# USB_HUB1_UP_PORT0.net
KiCad netlist of a schematic drawn in Altium Designer
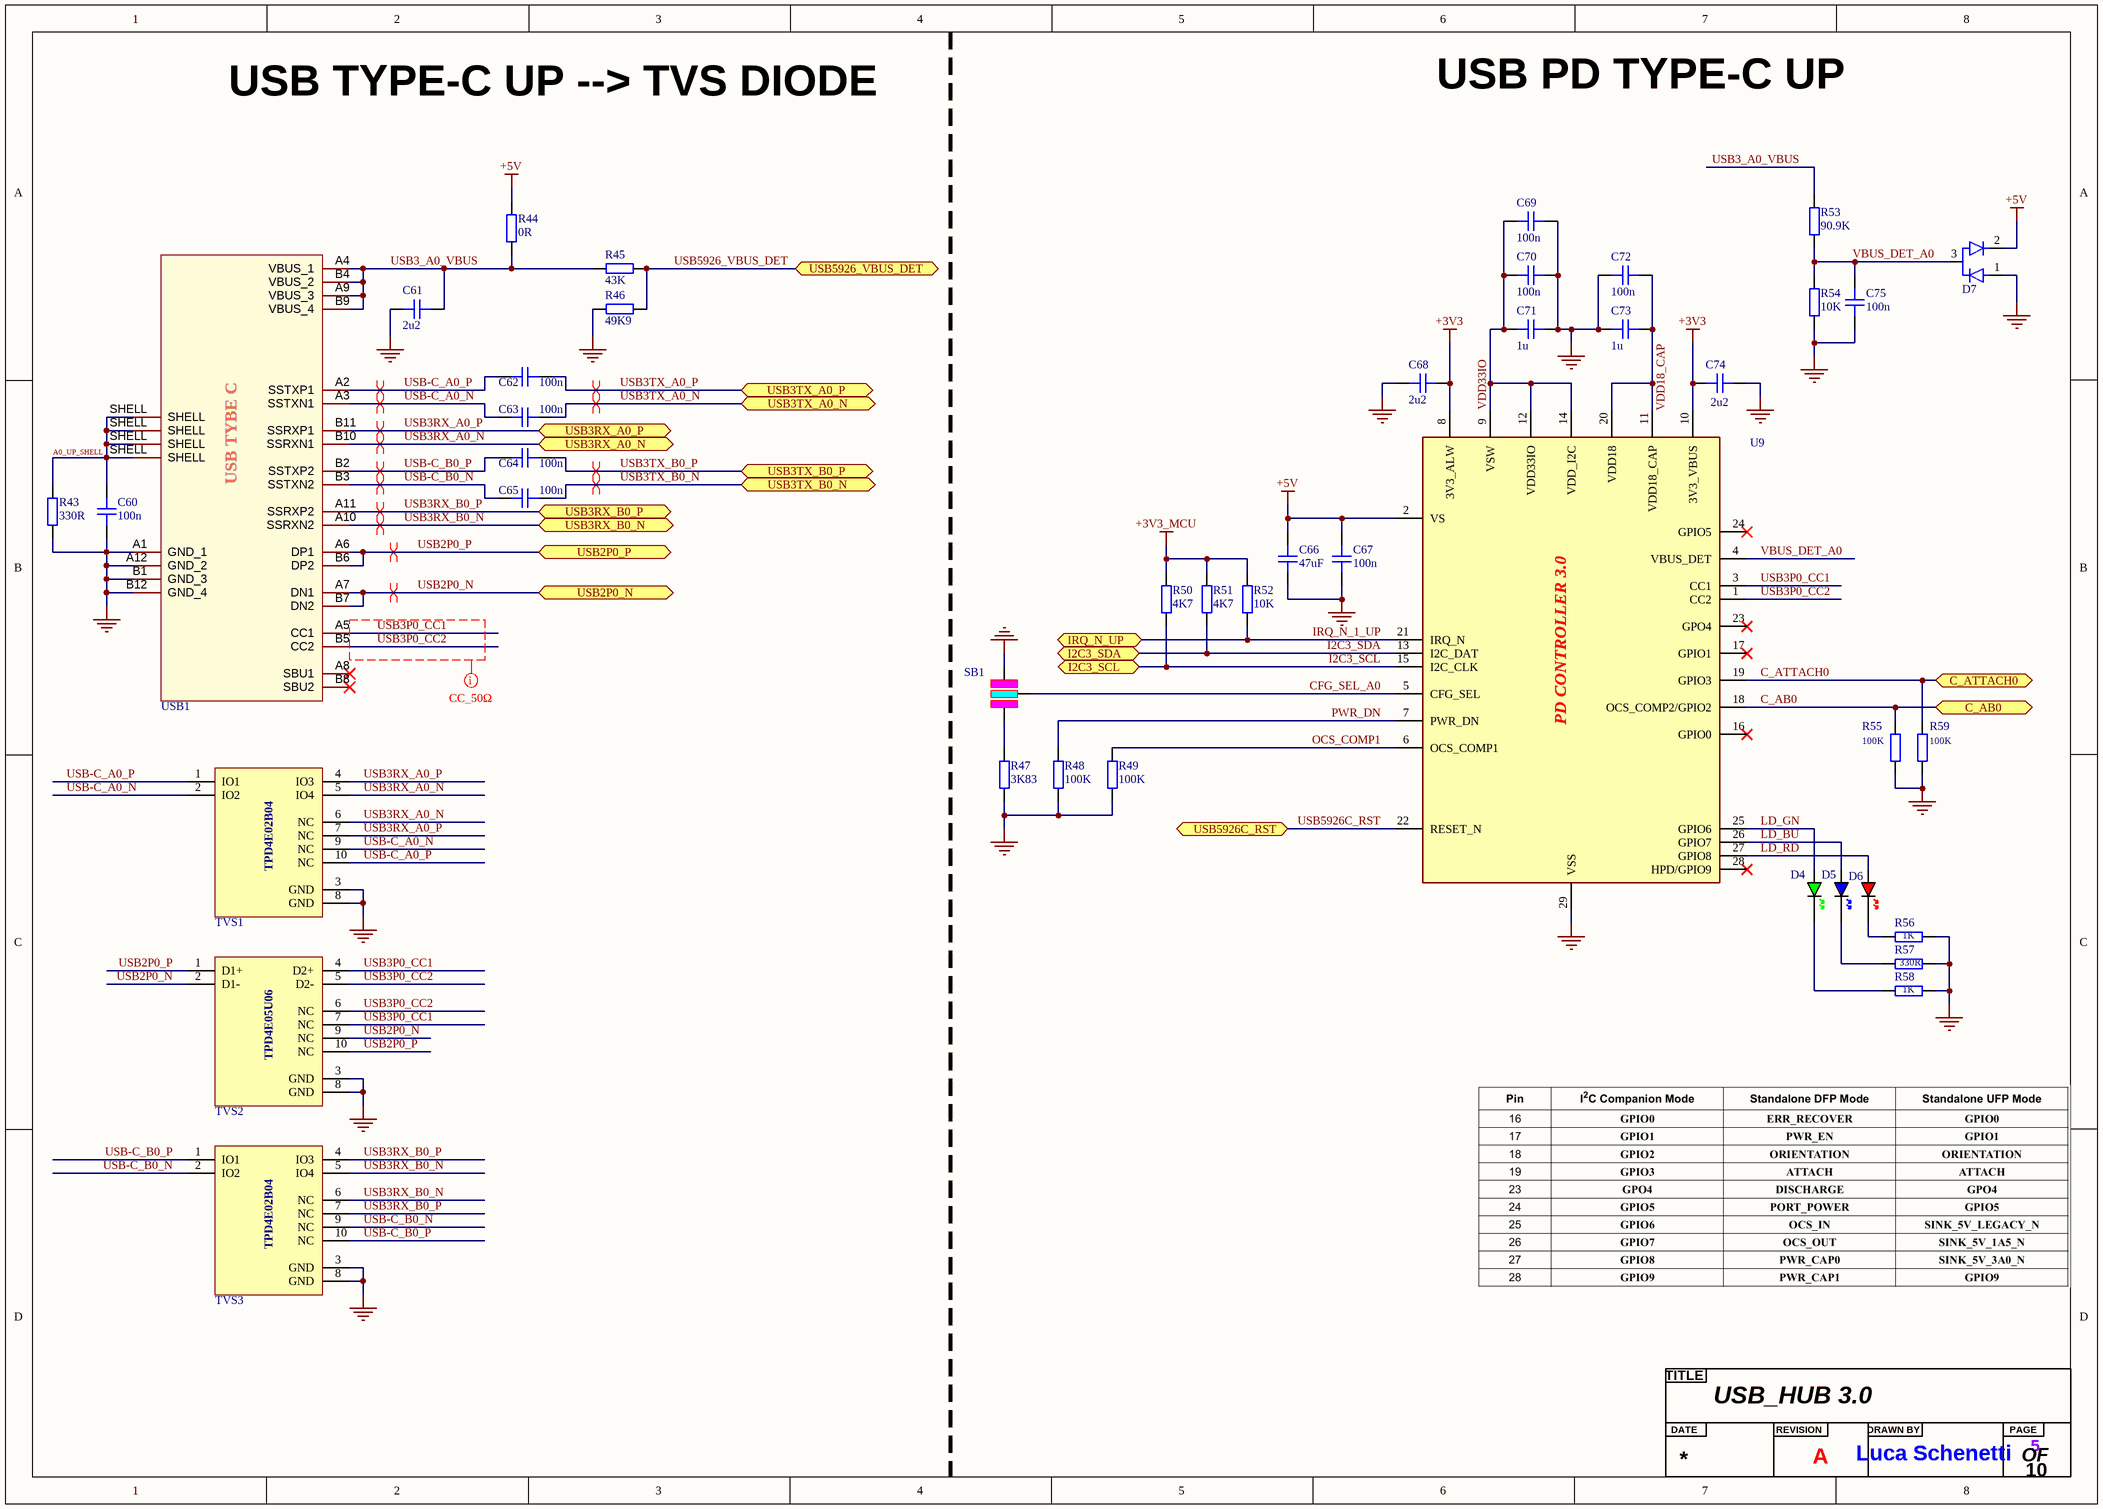
[diagram p0: USB_HUB1 UP PORT0.SchDoc]

(export (version "E")
  (design (tool "Eeschema 10.0.6"))
  (components
    (comp (ref "C60")
      (value "100n")
      (footprint "CAP_0603")
      (description "Capacitor SMD 0603 [C14663]")
      (libsource (lib "Schematic-Lib-PhilsLab") (part "CAP_0603"))
    )
    (comp (ref "C61")
      (value "2u2")
      (footprint "CAP_0603")
      (description "Capacitor SMD 0603 [C23630]")
      (libsource (lib "Schematic-Lib-PhilsLab") (part "CAP_0603"))
    )
    (comp (ref "C62")
      (value "100n")
      (footprint "CAP_0402")
      (description "Capacitor SMD 0402[C1525]")
      (libsource (lib "Schematic-Lib-PhilsLab") (part "CAP_0402"))
    )
    (comp (ref "C63")
      (value "100n")
      (footprint "CAP_0402")
      (description "Capacitor SMD 0402[C1525]")
      (libsource (lib "Schematic-Lib-PhilsLab") (part "CAP_0402"))
    )
    (comp (ref "C64")
      (value "100n")
      (footprint "CAP_0402")
      (description "Capacitor SMD 0402[C1525]")
      (libsource (lib "Schematic-Lib-PhilsLab") (part "CAP_0402"))
    )
    (comp (ref "C65")
      (value "100n")
      (footprint "CAP_0402")
      (description "Capacitor SMD 0402[C1525]")
      (libsource (lib "Schematic-Lib-PhilsLab") (part "CAP_0402"))
    )
    (comp (ref "C66")
      (value "47uF")
      (footprint "CAP_0603")
      (description "Capacitor SMD 0603 [C730416]")
      (libsource (lib "Schematic-Lib-PhilsLab") (part "CAP_0603"))
    )
    (comp (ref "C67")
      (value "100n")
      (footprint "CAP_0603")
      (description "Capacitor SMD 0603 [C14663]")
      (libsource (lib "Schematic-Lib-PhilsLab") (part "CAP_0603"))
    )
    (comp (ref "C68")
      (value "2u2")
      (footprint "CAP_0603")
      (description "Capacitor SMD 0603 [C23630]")
      (libsource (lib "Schematic-Lib-PhilsLab") (part "CAP_0603"))
    )
    (comp (ref "C69")
      (value "100n")
      (footprint "CAP_0603")
      (description "Capacitor SMD 0603 [C14663]")
      (libsource (lib "Schematic-Lib-PhilsLab") (part "CAP_0603"))
    )
    (comp (ref "C70")
      (value "100n")
      (footprint "CAP_0603")
      (description "Capacitor SMD 0603 [C14663]")
      (libsource (lib "Schematic-Lib-PhilsLab") (part "CAP_0603"))
    )
    (comp (ref "C71")
      (value "1u")
      (footprint "CAP_0603")
      (description "Capacitor SMD 0603 [C15849]")
      (libsource (lib "Schematic-Lib-PhilsLab") (part "CAP_0603"))
    )
    (comp (ref "C72")
      (value "100n")
      (footprint "CAP_0603")
      (description "Capacitor SMD 0603 [C14663]")
      (libsource (lib "Schematic-Lib-PhilsLab") (part "CAP_0603"))
    )
    (comp (ref "C73")
      (value "1u")
      (footprint "CAP_0603")
      (description "Capacitor SMD 0603 [C15849]")
      (libsource (lib "Schematic-Lib-PhilsLab") (part "CAP_0603"))
    )
    (comp (ref "C74")
      (value "2u2")
      (footprint "CAP_0603")
      (description "Capacitor SMD 0603 [C23630]")
      (libsource (lib "Schematic-Lib-PhilsLab") (part "CAP_0603"))
    )
    (comp (ref "C75")
      (value "100n")
      (footprint "CAP_0603")
      (description "Capacitor SMD 0603 [C14663]")
      (libsource (lib "Schematic-Lib-PhilsLab") (part "CAP_0603"))
    )
    (comp (ref "D4")
      (value "GREEN")
      (footprint "LED_0603_GREEN")
      (description "[C2986059]")
      (libsource (lib "Schematic-Lib-PhilsLab") (part "LED_0603_GREEN"))
    )
    (comp (ref "D5")
      (value "BLUE")
      (footprint "LED_0603_BLUE")
      (description "[C84266]")
      (libsource (lib "Schematic-Lib-PhilsLab") (part "LED_0603_BLUE"))
    )
    (comp (ref "D6")
      (value "RED")
      (footprint "LED_0603_RED")
      (description "[C2286]")
      (libsource (lib "Schematic-Lib-PhilsLab") (part "LED_0603_RED"))
    )
    (comp (ref "D7")
      (value "High-Speed Switching Diode")
      (footprint "BAV99,215")
      (description "[C2500]")
      (libsource (lib "My_Library") (part "BAV99,215"))
    )
    (comp (ref "R43")
      (value "330R")
      (footprint "RES_0603")
      (description "[C23138]")
      (libsource (lib "Schematic-Lib-PhilsLab") (part "RES_0603"))
    )
    (comp (ref "R44")
      (value "0R")
      (footprint "RES_0603")
      (description "[C21189]")
      (libsource (lib "Schematic-Lib-PhilsLab") (part "RES_0603"))
    )
    (comp (ref "R45")
      (value "43K")
      (footprint "RES_0603")
      (description "[C23172]")
      (libsource (lib "Schematic-Lib-PhilsLab") (part "RES_0603"))
    )
    (comp (ref "R46")
      (value "49K9")
      (footprint "RES_0603")
      (description "[C23184]")
      (libsource (lib "Schematic-Lib-PhilsLab") (part "RES_0603"))
    )
    (comp (ref "R47")
      (value "3K83")
      (footprint "RES_0603")
      (description "[C22982]")
      (libsource (lib "Schematic-Lib-PhilsLab") (part "RES_0603"))
    )
    (comp (ref "R48")
      (value "100K")
      (footprint "RES_0603")
      (description "[C25803]")
      (libsource (lib "Schematic-Lib-PhilsLab") (part "RES_0603"))
    )
    (comp (ref "R49")
      (value "100K")
      (footprint "RES_0603")
      (description "[C25803]")
      (libsource (lib "Schematic-Lib-PhilsLab") (part "RES_0603"))
    )
    (comp (ref "R50")
      (value "4K7")
      (footprint "RES_0603")
      (description "Resistor SMD 0603[C23162]")
      (libsource (lib "Schematic-Lib-PhilsLab") (part "RES_0603"))
    )
    (comp (ref "R51")
      (value "4K7")
      (footprint "RES_0603")
      (description "Resistor SMD 0603[C23162]")
      (libsource (lib "Schematic-Lib-PhilsLab") (part "RES_0603"))
    )
    (comp (ref "R52")
      (value "10K")
      (footprint "RES_0603")
      (description "Resistor SMD 0603[C25804]")
      (libsource (lib "Schematic-Lib-PhilsLab") (part "RES_0603"))
    )
    (comp (ref "R53")
      (value "90.9K")
      (footprint "RES_0603")
      (description "[C23129]")
      (libsource (lib "Schematic-Lib-PhilsLab") (part "RES_0603"))
    )
    (comp (ref "R54")
      (value "10K")
      (footprint "RES_0603")
      (description "[C25804]")
      (libsource (lib "Schematic-Lib-PhilsLab") (part "RES_0603"))
    )
    (comp (ref "R55")
      (value "100K")
      (footprint "RES_0603")
      (description "[C25803]")
      (libsource (lib "Schematic-Lib-PhilsLab") (part "RES_0603"))
    )
    (comp (ref "R56")
      (value "1K")
      (footprint "RES_0603")
      (description "[C21190]")
      (libsource (lib "Schematic-Lib-PhilsLab") (part "RES_0603"))
    )
    (comp (ref "R57")
      (value "330R")
      (footprint "RES_0603")
      (description "[C23138]")
      (libsource (lib "Schematic-Lib-PhilsLab") (part "RES_0603"))
    )
    (comp (ref "R58")
      (value "1K")
      (footprint "RES_0603")
      (description "[C21190]")
      (libsource (lib "Schematic-Lib-PhilsLab") (part "RES_0603"))
    )
    (comp (ref "R59")
      (value "100K")
      (footprint "RES_0603")
      (description "[C25803]")
      (libsource (lib "Schematic-Lib-PhilsLab") (part "RES_0603"))
    )
    (comp (ref "SB1")
      (value "SOLDER BBRIDGE 3W")
      (footprint "SOLDER BRIDBE 3W")
      (libsource (lib "My_Library") (part "SOLDER BBRIDGE 3W"))
    )
    (comp (ref "TVS1")
      (value "TVS DIODE USB 3")
      (footprint "TPD4E02B04DQAR")
      (description "[C106794]")
      (libsource (lib "My_Library") (part "TPD4E02B04DQAR"))
    )
    (comp (ref "TVS2")
      (value "ESD and Surge Protection USB, HDMI & High Speed")
      (footprint "TPD4E05U06DQAR")
      (description "[C138714]")
      (libsource (lib "My_Library") (part "TPD4E05U06DQAR"))
    )
    (comp (ref "TVS3")
      (value "TVS DIODE USB 3")
      (footprint "TPD4E02B04DQAR")
      (description "[C106794]")
      (libsource (lib "My_Library") (part "TPD4E02B04DQAR"))
    )
    (comp (ref "U9")
      (value "USB Type-C® PD 3.0 Port Controller")
      (footprint "UPD350AT/Q8X")
      (description "[C622602]")
      (libsource (lib "My_Library") (part "UPD350AT/Q8X"))
    )
    (comp (ref "USB1")
      (value "TYPE-C 24P QCHT")
      (footprint "TYPE-C 24P QCHT")
      (description "[C456013]")
      (libsource (lib "My_Library") (part "TYPE-C 24P QCHT"))
    )
  )
  (nets
    (net (code "1") (name "+3V3") (class "Default")
      (node (ref "C68") (pin "2") (pinfunction "2_2") (pintype "passive"))
      (node (ref "C74") (pin "2") (pinfunction "2_2") (pintype "passive"))
      (node (ref "U9") (pin "10") (pinfunction "3V3_VBUS_10") (pintype "passive"))
      (node (ref "U9") (pin "8") (pinfunction "3V3_ALW_8") (pintype "passive"))
    )
    (net (code "2") (name "+3V3_MCU") (class "Default")
      (node (ref "R50") (pin "2") (pinfunction "2_2") (pintype "passive"))
      (node (ref "R51") (pin "2") (pinfunction "2_2") (pintype "passive"))
      (node (ref "R52") (pin "2") (pinfunction "2_2") (pintype "passive"))
    )
    (net (code "3") (name "+5V") (class "Default")
      (node (ref "C66") (pin "2") (pinfunction "2_2") (pintype "passive"))
      (node (ref "C67") (pin "2") (pinfunction "2_2") (pintype "passive"))
      (node (ref "D7") (pin "2") (pinfunction "2_2") (pintype "passive"))
      (node (ref "R44") (pin "2") (pinfunction "2_2") (pintype "passive"))
      (node (ref "U9") (pin "2") (pinfunction "VS_2") (pintype "passive"))
    )
    (net (code "4") (name "/A0_UP_SHELL") (class "Default")
      (node (ref "C60") (pin "2") (pinfunction "2_2") (pintype "passive"))
      (node (ref "R43") (pin "2") (pinfunction "2_2") (pintype "passive"))
      (node (ref "USB1") (pin "SHELL") (pinfunction "SHELL_SHELL") (pintype "passive"))
    )
    (net (code "5") (name "/CFG_SEL_A0") (class "Default")
      (node (ref "SB1") (pin "1") (pinfunction "1_1") (pintype "passive"))
      (node (ref "U9") (pin "5") (pinfunction "CFG_SEL_5") (pintype "passive"))
    )
    (net (code "6") (name "/C_AB0") (class "Default")
      (node (ref "R55") (pin "2") (pinfunction "2_2") (pintype "passive"))
      (node (ref "U9") (pin "18") (pinfunction "OCS_COMP2/GPIO2_18") (pintype "passive"))
    )
    (net (code "7") (name "/C_ATTACH0") (class "Default")
      (node (ref "R59") (pin "2") (pinfunction "2_2") (pintype "passive"))
      (node (ref "U9") (pin "19") (pinfunction "GPIO3_19") (pintype "passive"))
    )
    (net (code "8") (name "/I2C3_SCL") (class "Default")
      (node (ref "R50") (pin "1") (pinfunction "1_1") (pintype "passive"))
      (node (ref "U9") (pin "15") (pinfunction "I2C_CLK_15") (pintype "passive"))
    )
    (net (code "9") (name "/I2C3_SDA") (class "Default")
      (node (ref "R51") (pin "1") (pinfunction "1_1") (pintype "passive"))
      (node (ref "U9") (pin "13") (pinfunction "I2C_DAT_13") (pintype "passive"))
    )
    (net (code "10") (name "/IRQ_N_1_UP") (class "Default")
      (node (ref "R52") (pin "1") (pinfunction "1_1") (pintype "passive"))
      (node (ref "U9") (pin "21") (pinfunction "IRQ_N_21") (pintype "passive"))
    )
    (net (code "12") (name "/LD_BU") (class "Default")
      (node (ref "D5") (pin "A") (pinfunction "A_A") (pintype "passive"))
      (node (ref "U9") (pin "26") (pinfunction "GPIO7_26") (pintype "passive"))
    )
    (net (code "13") (name "/LD_GN") (class "Default")
      (node (ref "D4") (pin "A") (pinfunction "A_A") (pintype "passive"))
      (node (ref "U9") (pin "25") (pinfunction "GPIO6_25") (pintype "passive"))
    )
    (net (code "14") (name "/LD_RD") (class "Default")
      (node (ref "D6") (pin "A") (pinfunction "A_A") (pintype "passive"))
      (node (ref "U9") (pin "27") (pinfunction "GPIO8_27") (pintype "passive"))
    )
    (net (code "15") (name "/OCS_COMP1") (class "Default")
      (node (ref "R49") (pin "2") (pinfunction "2_2") (pintype "passive"))
      (node (ref "U9") (pin "6") (pinfunction "OCS_COMP1_6") (pintype "passive"))
    )
    (net (code "16") (name "/PWR_DN") (class "Default")
      (node (ref "R48") (pin "2") (pinfunction "2_2") (pintype "passive"))
      (node (ref "U9") (pin "7") (pinfunction "PWR_DN_7") (pintype "passive"))
    )
    (net (code "17") (name "/USB-C_A0_N") (class "Default")
      (node (ref "C63") (pin "1") (pinfunction "1_1") (pintype "passive"))
      (node (ref "TVS1") (pin "2") (pinfunction "IO2_2") (pintype "passive"))
      (node (ref "TVS1") (pin "9") (pinfunction "NC_9") (pintype "passive"))
      (node (ref "USB1") (pin "A3") (pinfunction "SSTXN1_A3") (pintype "passive"))
    )
    (net (code "18") (name "/USB-C_A0_P") (class "Default")
      (node (ref "C62") (pin "1") (pinfunction "1_1") (pintype "passive"))
      (node (ref "TVS1") (pin "1") (pinfunction "IO1_1") (pintype "passive"))
      (node (ref "TVS1") (pin "10") (pinfunction "NC_10") (pintype "passive"))
      (node (ref "USB1") (pin "A2") (pinfunction "SSTXP1_A2") (pintype "passive"))
    )
    (net (code "19") (name "/USB-C_B0_N") (class "Default")
      (node (ref "C65") (pin "1") (pinfunction "1_1") (pintype "passive"))
      (node (ref "TVS3") (pin "2") (pinfunction "IO2_2") (pintype "passive"))
      (node (ref "TVS3") (pin "9") (pinfunction "NC_9") (pintype "passive"))
      (node (ref "USB1") (pin "B3") (pinfunction "SSTXN2_B3") (pintype "passive"))
    )
    (net (code "20") (name "/USB-C_B0_P") (class "Default")
      (node (ref "C64") (pin "1") (pinfunction "1_1") (pintype "passive"))
      (node (ref "TVS3") (pin "1") (pinfunction "IO1_1") (pintype "passive"))
      (node (ref "TVS3") (pin "10") (pinfunction "NC_10") (pintype "passive"))
      (node (ref "USB1") (pin "B2") (pinfunction "SSTXP2_B2") (pintype "passive"))
    )
    (net (code "21") (name "/USB2P0_N") (class "Default")
      (node (ref "TVS2") (pin "2") (pinfunction "D1-_2") (pintype "passive"))
      (node (ref "TVS2") (pin "9") (pinfunction "NC_9") (pintype "passive"))
      (node (ref "USB1") (pin "A7") (pinfunction "DN1_A7") (pintype "passive"))
      (node (ref "USB1") (pin "B7") (pinfunction "DN2_B7") (pintype "passive"))
    )
    (net (code "22") (name "/USB2P0_P") (class "Default")
      (node (ref "TVS2") (pin "1") (pinfunction "D1+_1") (pintype "passive"))
      (node (ref "TVS2") (pin "10") (pinfunction "NC_10") (pintype "passive"))
      (node (ref "USB1") (pin "A6") (pinfunction "DP1_A6") (pintype "passive"))
      (node (ref "USB1") (pin "B6") (pinfunction "DP2_B6") (pintype "passive"))
    )
    (net (code "23") (name "/USB3P0_CC1") (class "Default")
      (node (ref "TVS2") (pin "4") (pinfunction "D2+_4") (pintype "passive"))
      (node (ref "TVS2") (pin "7") (pinfunction "NC_7") (pintype "passive"))
      (node (ref "U9") (pin "3") (pinfunction "CC1_3") (pintype "passive"))
      (node (ref "USB1") (pin "A5") (pinfunction "CC1_A5") (pintype "passive"))
    )
    (net (code "24") (name "/USB3P0_CC2") (class "Default")
      (node (ref "TVS2") (pin "5") (pinfunction "D2-_5") (pintype "passive"))
      (node (ref "TVS2") (pin "6") (pinfunction "NC_6") (pintype "passive"))
      (node (ref "U9") (pin "1") (pinfunction "CC2_1") (pintype "passive"))
      (node (ref "USB1") (pin "B5") (pinfunction "CC2_B5") (pintype "passive"))
    )
    (net (code "25") (name "/USB3RX_A0_N") (class "Default")
      (node (ref "TVS1") (pin "5") (pinfunction "IO4_5") (pintype "passive"))
      (node (ref "TVS1") (pin "6") (pinfunction "NC_6") (pintype "passive"))
      (node (ref "USB1") (pin "B10") (pinfunction "SSRXN1_B10") (pintype "passive"))
    )
    (net (code "26") (name "/USB3RX_A0_P") (class "Default")
      (node (ref "TVS1") (pin "4") (pinfunction "IO3_4") (pintype "passive"))
      (node (ref "TVS1") (pin "7") (pinfunction "NC_7") (pintype "passive"))
      (node (ref "USB1") (pin "B11") (pinfunction "SSRXP1_B11") (pintype "passive"))
    )
    (net (code "27") (name "/USB3RX_B0_N") (class "Default")
      (node (ref "TVS3") (pin "5") (pinfunction "IO4_5") (pintype "passive"))
      (node (ref "TVS3") (pin "6") (pinfunction "NC_6") (pintype "passive"))
      (node (ref "USB1") (pin "A10") (pinfunction "SSRXN2_A10") (pintype "passive"))
    )
    (net (code "28") (name "/USB3RX_B0_P") (class "Default")
      (node (ref "TVS3") (pin "4") (pinfunction "IO3_4") (pintype "passive"))
      (node (ref "TVS3") (pin "7") (pinfunction "NC_7") (pintype "passive"))
      (node (ref "USB1") (pin "A11") (pinfunction "SSRXP2_A11") (pintype "passive"))
    )
    (net (code "29") (name "/USB3TX_A0_N") (class "Default")
      (node (ref "C63") (pin "2") (pinfunction "2_2") (pintype "passive"))
    )
    (net (code "30") (name "/USB3TX_A0_P") (class "Default")
      (node (ref "C62") (pin "2") (pinfunction "2_2") (pintype "passive"))
    )
    (net (code "31") (name "/USB3TX_B0_N") (class "Default")
      (node (ref "C65") (pin "2") (pinfunction "2_2") (pintype "passive"))
    )
    (net (code "32") (name "/USB3TX_B0_P") (class "Default")
      (node (ref "C64") (pin "2") (pinfunction "2_2") (pintype "passive"))
    )
    (net (code "33") (name "/USB3_A0_VBUS") (class "Default")
      (node (ref "C61") (pin "2") (pinfunction "2_2") (pintype "passive"))
      (node (ref "R44") (pin "1") (pinfunction "1_1") (pintype "passive"))
      (node (ref "R45") (pin "1") (pinfunction "1_1") (pintype "passive"))
      (node (ref "R53") (pin "2") (pinfunction "2_2") (pintype "passive"))
      (node (ref "USB1") (pin "A4") (pinfunction "VBUS_1_A4") (pintype "passive"))
      (node (ref "USB1") (pin "A9") (pinfunction "VBUS_3_A9") (pintype "passive"))
      (node (ref "USB1") (pin "B4") (pinfunction "VBUS_2_B4") (pintype "passive"))
      (node (ref "USB1") (pin "B9") (pinfunction "VBUS_4_B9") (pintype "passive"))
    )
    (net (code "34") (name "/USB5926C_RST") (class "Default")
      (node (ref "U9") (pin "22") (pinfunction "RESET_N_22") (pintype "passive"))
    )
    (net (code "35") (name "/USB5926_VBUS_DET") (class "Default")
      (node (ref "R45") (pin "2") (pinfunction "2_2") (pintype "passive"))
      (node (ref "R46") (pin "2") (pinfunction "2_2") (pintype "passive"))
    )
    (net (code "36") (name "/VBUS_DET_A0") (class "Default")
      (node (ref "C75") (pin "2") (pinfunction "2_2") (pintype "passive"))
      (node (ref "D7") (pin "3") (pinfunction "3_3") (pintype "passive"))
      (node (ref "R53") (pin "1") (pinfunction "1_1") (pintype "passive"))
      (node (ref "R54") (pin "2") (pinfunction "2_2") (pintype "passive"))
      (node (ref "U9") (pin "4") (pinfunction "VBUS_DET_4") (pintype "passive"))
    )
    (net (code "37") (name "/VDD18_CAP") (class "Default")
      (node (ref "C72") (pin "1") (pinfunction "1_1") (pintype "passive"))
      (node (ref "C73") (pin "2") (pinfunction "2_2") (pintype "passive"))
      (node (ref "U9") (pin "11") (pinfunction "VDD18_CAP_11") (pintype "passive"))
      (node (ref "U9") (pin "20") (pinfunction "VDD18_20") (pintype "passive"))
    )
    (net (code "38") (name "/VDD33IO") (class "Default")
      (node (ref "C69") (pin "2") (pinfunction "2_2") (pintype "passive"))
      (node (ref "C70") (pin "2") (pinfunction "2_2") (pintype "passive"))
      (node (ref "C71") (pin "2") (pinfunction "2_2") (pintype "passive"))
      (node (ref "U9") (pin "12") (pinfunction "VDD33IO_12") (pintype "passive"))
      (node (ref "U9") (pin "14") (pinfunction "VDD_I2C_14") (pintype "passive"))
      (node (ref "U9") (pin "9") (pinfunction "VSW_9") (pintype "passive"))
    )
    (net (code "39") (name "GND") (class "Default")
      (node (ref "C60") (pin "1") (pinfunction "1_1") (pintype "passive"))
      (node (ref "C61") (pin "1") (pinfunction "1_1") (pintype "passive"))
      (node (ref "C66") (pin "1") (pinfunction "1_1") (pintype "passive"))
      (node (ref "C67") (pin "1") (pinfunction "1_1") (pintype "passive"))
      (node (ref "C68") (pin "1") (pinfunction "1_1") (pintype "passive"))
      (node (ref "C69") (pin "1") (pinfunction "1_1") (pintype "passive"))
      (node (ref "C70") (pin "1") (pinfunction "1_1") (pintype "passive"))
      (node (ref "C71") (pin "1") (pinfunction "1_1") (pintype "passive"))
      (node (ref "C72") (pin "2") (pinfunction "2_2") (pintype "passive"))
      (node (ref "C73") (pin "1") (pinfunction "1_1") (pintype "passive"))
      (node (ref "C74") (pin "1") (pinfunction "1_1") (pintype "passive"))
      (node (ref "C75") (pin "1") (pinfunction "1_1") (pintype "passive"))
      (node (ref "D7") (pin "1") (pinfunction "1_1") (pintype "passive"))
      (node (ref "R43") (pin "1") (pinfunction "1_1") (pintype "passive"))
      (node (ref "R46") (pin "1") (pinfunction "1_1") (pintype "passive"))
      (node (ref "R47") (pin "1") (pinfunction "1_1") (pintype "passive"))
      (node (ref "R48") (pin "1") (pinfunction "1_1") (pintype "passive"))
      (node (ref "R49") (pin "1") (pinfunction "1_1") (pintype "passive"))
      (node (ref "R54") (pin "1") (pinfunction "1_1") (pintype "passive"))
      (node (ref "R55") (pin "1") (pinfunction "1_1") (pintype "passive"))
      (node (ref "R56") (pin "2") (pinfunction "2_2") (pintype "passive"))
      (node (ref "R57") (pin "2") (pinfunction "2_2") (pintype "passive"))
      (node (ref "R58") (pin "2") (pinfunction "2_2") (pintype "passive"))
      (node (ref "R59") (pin "1") (pinfunction "1_1") (pintype "passive"))
      (node (ref "SB1") (pin "2") (pinfunction "2_2") (pintype "passive"))
      (node (ref "TVS1") (pin "3") (pinfunction "GND_3") (pintype "power_in"))
      (node (ref "TVS1") (pin "8") (pinfunction "GND_8") (pintype "power_in"))
      (node (ref "TVS2") (pin "3") (pinfunction "GND_3") (pintype "power_in"))
      (node (ref "TVS2") (pin "8") (pinfunction "GND_8") (pintype "power_in"))
      (node (ref "TVS3") (pin "3") (pinfunction "GND_3") (pintype "power_in"))
      (node (ref "TVS3") (pin "8") (pinfunction "GND_8") (pintype "power_in"))
      (node (ref "U9") (pin "29") (pinfunction "VSS_29") (pintype "passive"))
      (node (ref "USB1") (pin "A1") (pinfunction "GND_1_A1") (pintype "passive"))
      (node (ref "USB1") (pin "A12") (pinfunction "GND_2_A12") (pintype "passive"))
      (node (ref "USB1") (pin "B1") (pinfunction "GND_3_B1") (pintype "passive"))
      (node (ref "USB1") (pin "B12") (pinfunction "GND_4_B12") (pintype "passive"))
    )
    (net (code "40") (name "Net-(D4-PadK)") (class "Default")
      (node (ref "D4") (pin "K") (pinfunction "K_K") (pintype "passive"))
      (node (ref "R58") (pin "1") (pinfunction "1_1") (pintype "passive"))
    )
    (net (code "41") (name "Net-(D5-PadK)") (class "Default")
      (node (ref "D5") (pin "K") (pinfunction "K_K") (pintype "passive"))
      (node (ref "R57") (pin "1") (pinfunction "1_1") (pintype "passive"))
    )
    (net (code "42") (name "Net-(D6-PadK)") (class "Default")
      (node (ref "D6") (pin "K") (pinfunction "K_K") (pintype "passive"))
      (node (ref "R56") (pin "1") (pinfunction "1_1") (pintype "passive"))
    )
    (net (code "43") (name "Net-(R47-Pad2)") (class "Default")
      (node (ref "R47") (pin "2") (pinfunction "2_2") (pintype "passive"))
      (node (ref "SB1") (pin "0") (pinfunction "0_0") (pintype "passive"))
    )
    (net (code "44") (name "unconnected-(U9-GPIO0-Pad16)") (class "Default")
      (node (ref "U9") (pin "16") (pinfunction "GPIO0_16") (pintype "passive+no_connect"))
    )
    (net (code "45") (name "unconnected-(U9-GPIO1-Pad17)") (class "Default")
      (node (ref "U9") (pin "17") (pinfunction "GPIO1_17") (pintype "passive+no_connect"))
    )
    (net (code "46") (name "unconnected-(U9-GPIO5-Pad24)") (class "Default")
      (node (ref "U9") (pin "24") (pinfunction "GPIO5_24") (pintype "passive+no_connect"))
    )
    (net (code "47") (name "unconnected-(U9-GPO4-Pad23)") (class "Default")
      (node (ref "U9") (pin "23") (pinfunction "GPO4_23") (pintype "passive+no_connect"))
    )
    (net (code "48") (name "unconnected-(U9-HPD{slash}GPIO9-Pad28)") (class "Default")
      (node (ref "U9") (pin "28") (pinfunction "HPD/GPIO9_28") (pintype "passive+no_connect"))
    )
    (net (code "49") (name "unconnected-(USB1-SBU1-PadA8)") (class "Default")
      (node (ref "USB1") (pin "A8") (pinfunction "SBU1_A8") (pintype "passive+no_connect"))
    )
    (net (code "50") (name "unconnected-(USB1-SBU2-PadB8)") (class "Default")
      (node (ref "USB1") (pin "B8") (pinfunction "SBU2_B8") (pintype "passive+no_connect"))
    )
  )
)
